# MAGI_sRTC.net
KiCad netlist of a schematic drawn in Altium Designer
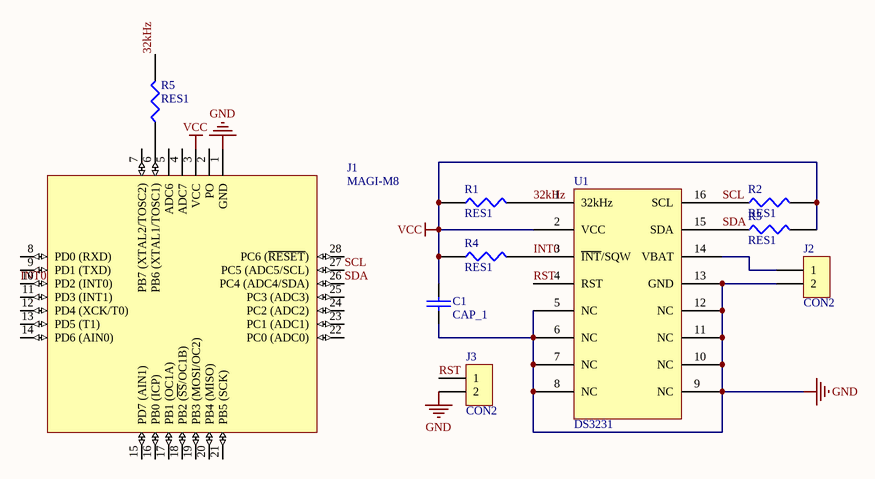
[diagram p0: MAGI'sRTC.SchDoc]

(export (version "E")
  (design (tool "Eeschema 10.0.6"))
  (components
    (comp (ref "C1")
      (value "CAP_1")
      (footprint "6-0805_M")
      (description "Capacitor")
      (libsource (lib "电容器") (part "CAP_1"))
    )
    (comp (ref "J1") (value "MAGI-M8") (footprint "MAGI-M8") (libsource (lib "MAGI-M8") (part "MAGI-M8")))
    (comp (ref "J2")
      (value "CON2")
      (footprint "CR1220")
      (description "Connector")
      (libsource (lib "CON系列") (part "CON2"))
    )
    (comp (ref "J3")
      (value "CON2")
      (footprint "SW-1-SMD")
      (description "Connector")
      (libsource (lib "CON系列") (part "CON2"))
    )
    (comp (ref "R1") (value "RES1") (footprint "6-0805_N") (libsource (lib "电阻器") (part "RES1")))
    (comp (ref "R2") (value "RES1") (footprint "6-0805_N") (libsource (lib "电阻器") (part "RES1")))
    (comp (ref "R3") (value "RES1") (footprint "6-0805_N") (libsource (lib "电阻器") (part "RES1")))
    (comp (ref "R4") (value "RES1") (footprint "6-0805_N") (libsource (lib "电阻器") (part "RES1")))
    (comp (ref "R5") (value "RES1") (footprint "6-0805_N") (libsource (lib "电阻器") (part "RES1")))
    (comp (ref "U1") (value "DS3231") (footprint "DS3231") (libsource (lib "RTC") (part "DS3231")))
  )
  (nets
    (net (code "1") (name "/32kHz") (class "Default")
      (node (ref "R1") (pin "2") (pinfunction "2_2") (pintype "passive"))
      (node (ref "R5") (pin "2") (pinfunction "2_2") (pintype "passive"))
      (node (ref "U1") (pin "1") (pinfunction "32kHz_1") (pintype "passive"))
    )
    (net (code "2") (name "/INT0") (class "Default")
      (node (ref "J1") (pin "10") (pinfunction "PD2_(INT0)_10") (pintype "bidirectional"))
      (node (ref "R4") (pin "2") (pinfunction "2_2") (pintype "passive"))
      (node (ref "U1") (pin "3") (pinfunction "~{INT}/SQW_3") (pintype "passive"))
    )
    (net (code "3") (name "/RST") (class "Default")
      (node (ref "J3") (pin "1") (pinfunction "1_1") (pintype "passive"))
      (node (ref "U1") (pin "4") (pinfunction "RST_4") (pintype "passive"))
    )
    (net (code "4") (name "/SCL") (class "Default")
      (node (ref "J1") (pin "27") (pinfunction "PC5_(ADC5/SCL)_27") (pintype "bidirectional"))
      (node (ref "R2") (pin "1") (pinfunction "1_1") (pintype "passive"))
      (node (ref "U1") (pin "16") (pinfunction "SCL_16") (pintype "passive"))
    )
    (net (code "5") (name "/SDA") (class "Default")
      (node (ref "J1") (pin "26") (pinfunction "PC4_(ADC4/SDA)_26") (pintype "bidirectional"))
      (node (ref "R3") (pin "1") (pinfunction "1_1") (pintype "passive"))
      (node (ref "U1") (pin "15") (pinfunction "SDA_15") (pintype "passive"))
    )
    (net (code "6") (name "GND") (class "Default")
      (node (ref "C1") (pin "2") (pinfunction "2_2") (pintype "passive"))
      (node (ref "J1") (pin "1") (pinfunction "GND_1") (pintype "power_in"))
      (node (ref "J2") (pin "2") (pinfunction "2_2") (pintype "passive"))
      (node (ref "J3") (pin "2") (pinfunction "2_2") (pintype "passive"))
      (node (ref "U1") (pin "10") (pinfunction "NC_10") (pintype "passive"))
      (node (ref "U1") (pin "11") (pinfunction "NC_11") (pintype "passive"))
      (node (ref "U1") (pin "12") (pinfunction "NC_12") (pintype "passive"))
      (node (ref "U1") (pin "13") (pinfunction "GND_13") (pintype "passive"))
      (node (ref "U1") (pin "5") (pinfunction "NC_5") (pintype "passive"))
      (node (ref "U1") (pin "6") (pinfunction "NC_6") (pintype "passive"))
      (node (ref "U1") (pin "7") (pinfunction "NC_7") (pintype "passive"))
      (node (ref "U1") (pin "8") (pinfunction "NC_8") (pintype "passive"))
      (node (ref "U1") (pin "9") (pinfunction "NC_9") (pintype "passive"))
    )
    (net (code "7") (name "Net-(J1-PB6_(XTAL1{slash}TOSC1))") (class "Default")
      (node (ref "J1") (pin "6") (pinfunction "PB6_(XTAL1/TOSC1)_6") (pintype "bidirectional"))
      (node (ref "R5") (pin "1") (pinfunction "1_1") (pintype "passive"))
    )
    (net (code "8") (name "Net-(U1-VBAT)") (class "Default")
      (node (ref "J2") (pin "1") (pinfunction "1_1") (pintype "passive"))
      (node (ref "U1") (pin "14") (pinfunction "VBAT_14") (pintype "passive"))
    )
    (net (code "9") (name "VCC") (class "Default")
      (node (ref "C1") (pin "1") (pinfunction "1_1") (pintype "passive"))
      (node (ref "J1") (pin "3") (pinfunction "VCC_3") (pintype "power_in"))
      (node (ref "R1") (pin "1") (pinfunction "1_1") (pintype "passive"))
      (node (ref "R2") (pin "2") (pinfunction "2_2") (pintype "passive"))
      (node (ref "R3") (pin "2") (pinfunction "2_2") (pintype "passive"))
      (node (ref "R4") (pin "1") (pinfunction "1_1") (pintype "passive"))
      (node (ref "U1") (pin "2") (pinfunction "VCC_2") (pintype "passive"))
    )
    (net (code "10") (name "unconnected-(J1-ADC6-Pad5)") (class "Default")
      (node (ref "J1") (pin "5") (pinfunction "ADC6_5") (pintype "passive"))
    )
    (net (code "11") (name "unconnected-(J1-ADC7-Pad4)") (class "Default")
      (node (ref "J1") (pin "4") (pinfunction "ADC7_4") (pintype "passive"))
    )
    (net (code "12") (name "unconnected-(J1-PB0_(ICP)-Pad16)") (class "Default")
      (node (ref "J1") (pin "16") (pinfunction "PB0_(ICP)_16") (pintype "bidirectional"))
    )
    (net (code "13") (name "unconnected-(J1-PB1_(OC1A)-Pad17)") (class "Default")
      (node (ref "J1") (pin "17") (pinfunction "PB1_(OC1A)_17") (pintype "bidirectional"))
    )
    (net (code "14") (name "unconnected-(J1-PB2_(~{SS}{slash}OC1B)-Pad18)") (class "Default")
      (node (ref "J1") (pin "18") (pinfunction "PB2_(~{SS}/OC1B)_18") (pintype "bidirectional"))
    )
    (net (code "15") (name "unconnected-(J1-PB3_(MOSI{slash}OC2)-Pad19)") (class "Default")
      (node (ref "J1") (pin "19") (pinfunction "PB3_(MOSI/OC2)_19") (pintype "bidirectional"))
    )
    (net (code "16") (name "unconnected-(J1-PB4_(MISO)-Pad20)") (class "Default")
      (node (ref "J1") (pin "20") (pinfunction "PB4_(MISO)_20") (pintype "bidirectional"))
    )
    (net (code "17") (name "unconnected-(J1-PB5_(SCK)-Pad21)") (class "Default")
      (node (ref "J1") (pin "21") (pinfunction "PB5_(SCK)_21") (pintype "bidirectional"))
    )
    (net (code "18") (name "unconnected-(J1-PB7_(XTAL2{slash}TOSC2)-Pad7)") (class "Default")
      (node (ref "J1") (pin "7") (pinfunction "PB7_(XTAL2/TOSC2)_7") (pintype "bidirectional"))
    )
    (net (code "19") (name "unconnected-(J1-PC0_(ADC0)-Pad22)") (class "Default")
      (node (ref "J1") (pin "22") (pinfunction "PC0_(ADC0)_22") (pintype "bidirectional"))
    )
    (net (code "20") (name "unconnected-(J1-PC1_(ADC1)-Pad23)") (class "Default")
      (node (ref "J1") (pin "23") (pinfunction "PC1_(ADC1)_23") (pintype "bidirectional"))
    )
    (net (code "21") (name "unconnected-(J1-PC2_(ADC2)-Pad24)") (class "Default")
      (node (ref "J1") (pin "24") (pinfunction "PC2_(ADC2)_24") (pintype "bidirectional"))
    )
    (net (code "22") (name "unconnected-(J1-PC3_(ADC3)-Pad25)") (class "Default")
      (node (ref "J1") (pin "25") (pinfunction "PC3_(ADC3)_25") (pintype "bidirectional"))
    )
    (net (code "23") (name "unconnected-(J1-PC6_(~{RESET})-Pad28)") (class "Default")
      (node (ref "J1") (pin "28") (pinfunction "PC6_(~{RESET})_28") (pintype "bidirectional"))
    )
    (net (code "24") (name "unconnected-(J1-PD0_(RXD)-Pad8)") (class "Default")
      (node (ref "J1") (pin "8") (pinfunction "PD0_(RXD)_8") (pintype "bidirectional"))
    )
    (net (code "25") (name "unconnected-(J1-PD1_(TXD)-Pad9)") (class "Default")
      (node (ref "J1") (pin "9") (pinfunction "PD1_(TXD)_9") (pintype "bidirectional"))
    )
    (net (code "26") (name "unconnected-(J1-PD3_(INT1)-Pad11)") (class "Default")
      (node (ref "J1") (pin "11") (pinfunction "PD3_(INT1)_11") (pintype "bidirectional"))
    )
    (net (code "27") (name "unconnected-(J1-PD4_(XCK{slash}T0)-Pad12)") (class "Default")
      (node (ref "J1") (pin "12") (pinfunction "PD4_(XCK/T0)_12") (pintype "bidirectional"))
    )
    (net (code "28") (name "unconnected-(J1-PD5_(T1)-Pad13)") (class "Default")
      (node (ref "J1") (pin "13") (pinfunction "PD5_(T1)_13") (pintype "bidirectional"))
    )
    (net (code "29") (name "unconnected-(J1-PD6_(AIN0)-Pad14)") (class "Default")
      (node (ref "J1") (pin "14") (pinfunction "PD6_(AIN0)_14") (pintype "bidirectional"))
    )
    (net (code "30") (name "unconnected-(J1-PD7_(AIN1)-Pad15)") (class "Default")
      (node (ref "J1") (pin "15") (pinfunction "PD7_(AIN1)_15") (pintype "bidirectional"))
    )
    (net (code "31") (name "unconnected-(J1-PO-Pad2)") (class "Default")
      (node (ref "J1") (pin "2") (pinfunction "PO_2") (pintype "power_in"))
    )
  )
)
